# AVRI2CIO_V0_2_LEVEL0.net
KiCad netlist of a schematic drawn in EAGLE
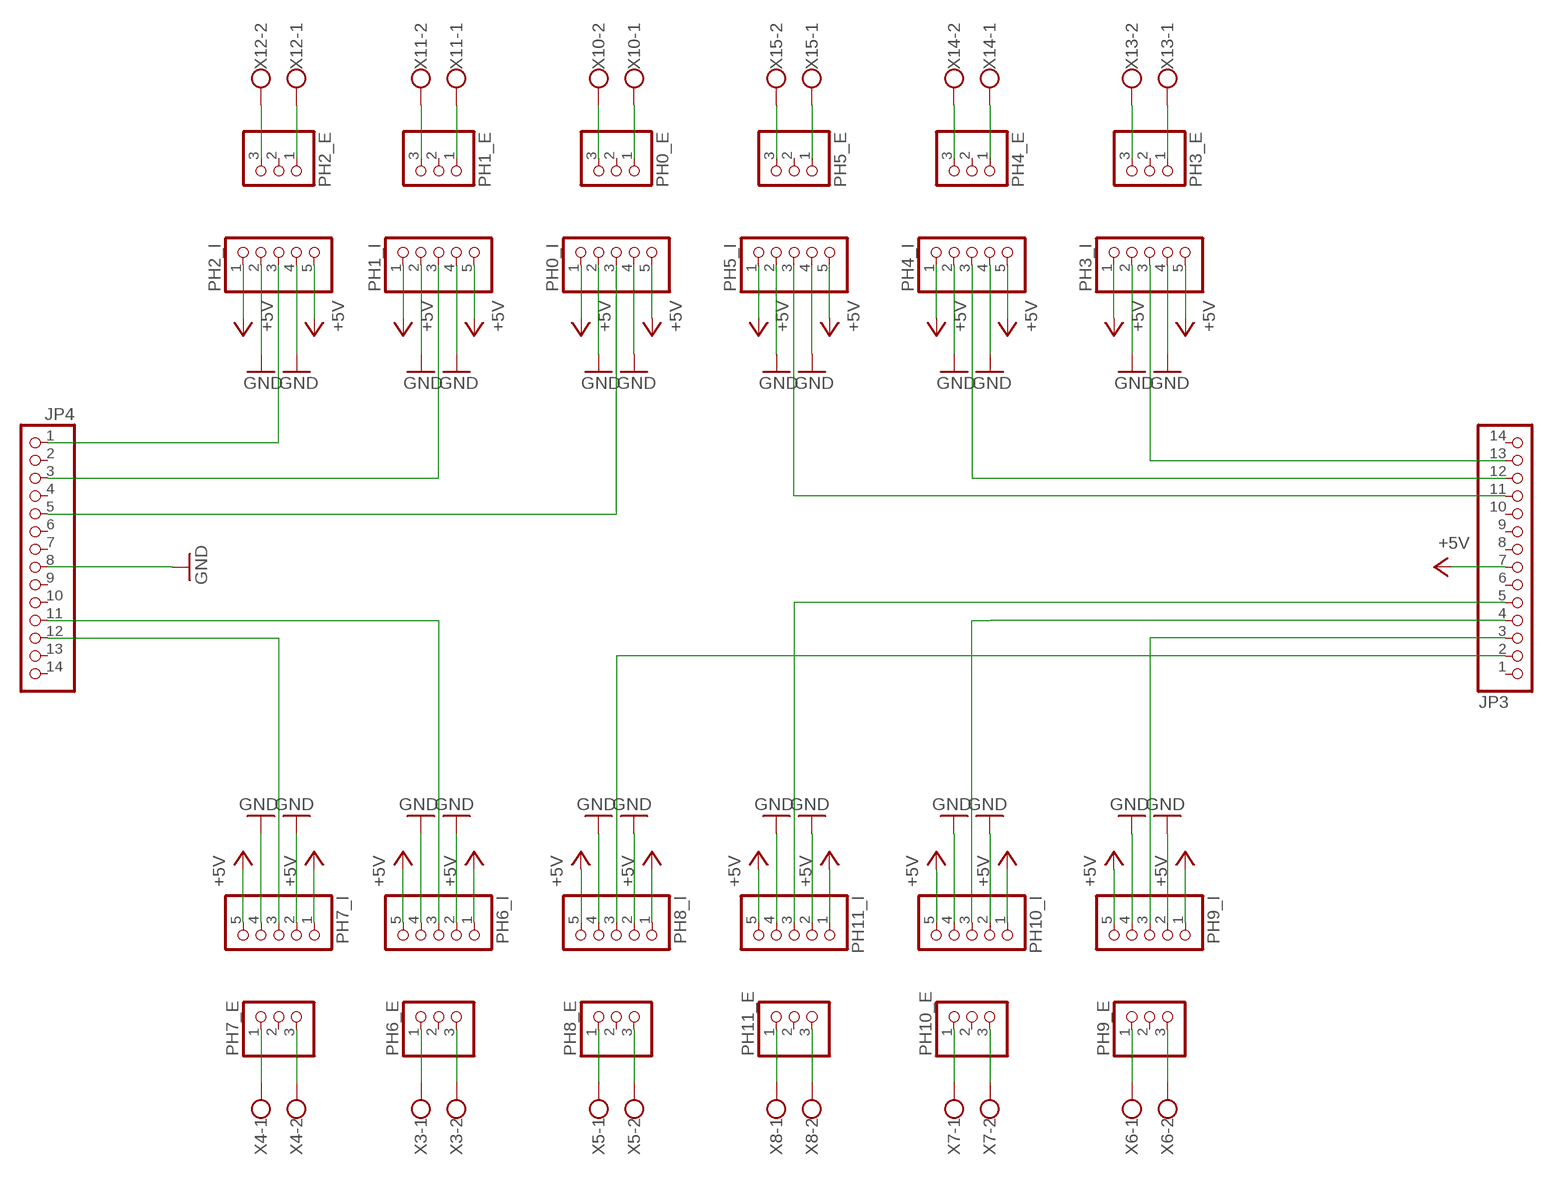
[diagram p0: schematic, sheet 1]

(export (version "E")
  (design (tool "Eeschema 10.0.6"))
  (components
    (comp (ref "JP3")
      (value "PINHD-1X14")
      (footprint "eagle-import:1X14")
      (libsource (lib "eagle-import") (part "PINHD-1X14"))
    )
    (comp (ref "JP4")
      (value "PINHD-1X14")
      (footprint "eagle-import:1X14")
      (libsource (lib "eagle-import") (part "PINHD-1X14"))
    )
    (comp (ref "PH0_E")
      (value "PINHD-1X3")
      (footprint "eagle-import:1X03")
      (libsource (lib "eagle-import") (part "PINHD-1X3"))
    )
    (comp (ref "PH0_I")
      (value "PINHD-1X5")
      (footprint "eagle-import:1X05")
      (libsource (lib "eagle-import") (part "PINHD-1X5"))
    )
    (comp (ref "PH1_E")
      (value "PINHD-1X3")
      (footprint "eagle-import:1X03")
      (libsource (lib "eagle-import") (part "PINHD-1X3"))
    )
    (comp (ref "PH1_I")
      (value "PINHD-1X5")
      (footprint "eagle-import:1X05")
      (libsource (lib "eagle-import") (part "PINHD-1X5"))
    )
    (comp (ref "PH2_E")
      (value "PINHD-1X3")
      (footprint "eagle-import:1X03")
      (libsource (lib "eagle-import") (part "PINHD-1X3"))
    )
    (comp (ref "PH2_I")
      (value "PINHD-1X5")
      (footprint "eagle-import:1X05")
      (libsource (lib "eagle-import") (part "PINHD-1X5"))
    )
    (comp (ref "PH3_E")
      (value "PINHD-1X3")
      (footprint "eagle-import:1X03")
      (libsource (lib "eagle-import") (part "PINHD-1X3"))
    )
    (comp (ref "PH3_I")
      (value "PINHD-1X5")
      (footprint "eagle-import:1X05")
      (libsource (lib "eagle-import") (part "PINHD-1X5"))
    )
    (comp (ref "PH4_E")
      (value "PINHD-1X3")
      (footprint "eagle-import:1X03")
      (libsource (lib "eagle-import") (part "PINHD-1X3"))
    )
    (comp (ref "PH4_I")
      (value "PINHD-1X5")
      (footprint "eagle-import:1X05")
      (libsource (lib "eagle-import") (part "PINHD-1X5"))
    )
    (comp (ref "PH5_E")
      (value "PINHD-1X3")
      (footprint "eagle-import:1X03")
      (libsource (lib "eagle-import") (part "PINHD-1X3"))
    )
    (comp (ref "PH5_I")
      (value "PINHD-1X5")
      (footprint "eagle-import:1X05")
      (libsource (lib "eagle-import") (part "PINHD-1X5"))
    )
    (comp (ref "PH6_E")
      (value "PINHD-1X3")
      (footprint "eagle-import:1X03")
      (libsource (lib "eagle-import") (part "PINHD-1X3"))
    )
    (comp (ref "PH6_I")
      (value "PINHD-1X5")
      (footprint "eagle-import:1X05")
      (libsource (lib "eagle-import") (part "PINHD-1X5"))
    )
    (comp (ref "PH7_E")
      (value "PINHD-1X3")
      (footprint "eagle-import:1X03")
      (libsource (lib "eagle-import") (part "PINHD-1X3"))
    )
    (comp (ref "PH7_I")
      (value "PINHD-1X5")
      (footprint "eagle-import:1X05")
      (libsource (lib "eagle-import") (part "PINHD-1X5"))
    )
    (comp (ref "PH8_E")
      (value "PINHD-1X3")
      (footprint "eagle-import:1X03")
      (libsource (lib "eagle-import") (part "PINHD-1X3"))
    )
    (comp (ref "PH8_I")
      (value "PINHD-1X5")
      (footprint "eagle-import:1X05")
      (libsource (lib "eagle-import") (part "PINHD-1X5"))
    )
    (comp (ref "PH9_E")
      (value "PINHD-1X3")
      (footprint "eagle-import:1X03")
      (libsource (lib "eagle-import") (part "PINHD-1X3"))
    )
    (comp (ref "PH9_I")
      (value "PINHD-1X5")
      (footprint "eagle-import:1X05")
      (libsource (lib "eagle-import") (part "PINHD-1X5"))
    )
    (comp (ref "PH10_E")
      (value "PINHD-1X3")
      (footprint "eagle-import:1X03")
      (libsource (lib "eagle-import") (part "PINHD-1X3"))
    )
    (comp (ref "PH10_I")
      (value "PINHD-1X5")
      (footprint "eagle-import:1X05")
      (libsource (lib "eagle-import") (part "PINHD-1X5"))
    )
    (comp (ref "PH11_E")
      (value "PINHD-1X3")
      (footprint "eagle-import:1X03")
      (libsource (lib "eagle-import") (part "PINHD-1X3"))
    )
    (comp (ref "PH11_I")
      (value "PINHD-1X5")
      (footprint "eagle-import:1X05")
      (libsource (lib "eagle-import") (part "PINHD-1X5"))
    )
    (comp (ref "X3")
      (value "W237-102")
      (footprint "eagle-import:W237-102")
      (fields (field (name "MPN") "237-102"))
      (libsource (lib "eagle-import") (part "W237-102"))
    )
    (comp (ref "X4")
      (value "W237-102")
      (footprint "eagle-import:W237-102")
      (fields (field (name "MPN") "237-102"))
      (libsource (lib "eagle-import") (part "W237-102"))
    )
    (comp (ref "X5")
      (value "W237-102")
      (footprint "eagle-import:W237-102")
      (fields (field (name "MPN") "237-102"))
      (libsource (lib "eagle-import") (part "W237-102"))
    )
    (comp (ref "X6")
      (value "W237-102")
      (footprint "eagle-import:W237-102")
      (fields (field (name "MPN") "237-102"))
      (libsource (lib "eagle-import") (part "W237-102"))
    )
    (comp (ref "X7")
      (value "W237-102")
      (footprint "eagle-import:W237-102")
      (fields (field (name "MPN") "237-102"))
      (libsource (lib "eagle-import") (part "W237-102"))
    )
    (comp (ref "X8")
      (value "W237-102")
      (footprint "eagle-import:W237-102")
      (fields (field (name "MPN") "237-102"))
      (libsource (lib "eagle-import") (part "W237-102"))
    )
    (comp (ref "X10")
      (value "W237-102")
      (footprint "eagle-import:W237-102")
      (fields
        (field (name "MPN") "237-102")
        (field (name "MPN_1") "237-102")
        (field (name "OC_FARNELL") "unknown")
        (field (name "OC_NEWARK") "70K9898")
      )
      (libsource (lib "eagle-import") (part "W237-102"))
    )
    (comp (ref "X11")
      (value "W237-102")
      (footprint "eagle-import:W237-102")
      (fields (field (name "MPN") "237-102"))
      (libsource (lib "eagle-import") (part "W237-102"))
    )
    (comp (ref "X12")
      (value "W237-102")
      (footprint "eagle-import:W237-102")
      (fields (field (name "MPN") "237-102"))
      (libsource (lib "eagle-import") (part "W237-102"))
    )
    (comp (ref "X13")
      (value "W237-102")
      (footprint "eagle-import:W237-102")
      (fields (field (name "MPN") "237-102"))
      (libsource (lib "eagle-import") (part "W237-102"))
    )
    (comp (ref "X14")
      (value "W237-102")
      (footprint "eagle-import:W237-102")
      (fields (field (name "MPN") "237-102"))
      (libsource (lib "eagle-import") (part "W237-102"))
    )
    (comp (ref "X15")
      (value "W237-102")
      (footprint "eagle-import:W237-102")
      (fields (field (name "MPN") "237-102"))
      (libsource (lib "eagle-import") (part "W237-102"))
    )
  )
  (nets
    (net (code "1") (name "+5V") (class "Default")
      (node (ref "JP3") (pin "7") (pinfunction "7_7") (pintype "passive"))
      (node (ref "PH0_I") (pin "1") (pinfunction "1_1") (pintype "passive"))
      (node (ref "PH0_I") (pin "5") (pinfunction "5_5") (pintype "passive"))
      (node (ref "PH10_I") (pin "1") (pinfunction "1_1") (pintype "passive"))
      (node (ref "PH10_I") (pin "5") (pinfunction "5_5") (pintype "passive"))
      (node (ref "PH11_I") (pin "1") (pinfunction "1_1") (pintype "passive"))
      (node (ref "PH11_I") (pin "5") (pinfunction "5_5") (pintype "passive"))
      (node (ref "PH1_I") (pin "1") (pinfunction "1_1") (pintype "passive"))
      (node (ref "PH1_I") (pin "5") (pinfunction "5_5") (pintype "passive"))
      (node (ref "PH2_I") (pin "1") (pinfunction "1_1") (pintype "passive"))
      (node (ref "PH2_I") (pin "5") (pinfunction "5_5") (pintype "passive"))
      (node (ref "PH3_I") (pin "1") (pinfunction "1_1") (pintype "passive"))
      (node (ref "PH3_I") (pin "5") (pinfunction "5_5") (pintype "passive"))
      (node (ref "PH4_I") (pin "1") (pinfunction "1_1") (pintype "passive"))
      (node (ref "PH4_I") (pin "5") (pinfunction "5_5") (pintype "passive"))
      (node (ref "PH5_I") (pin "1") (pinfunction "1_1") (pintype "passive"))
      (node (ref "PH5_I") (pin "5") (pinfunction "5_5") (pintype "passive"))
      (node (ref "PH6_I") (pin "1") (pinfunction "1_1") (pintype "passive"))
      (node (ref "PH6_I") (pin "5") (pinfunction "5_5") (pintype "passive"))
      (node (ref "PH7_I") (pin "1") (pinfunction "1_1") (pintype "passive"))
      (node (ref "PH7_I") (pin "5") (pinfunction "5_5") (pintype "passive"))
      (node (ref "PH8_I") (pin "1") (pinfunction "1_1") (pintype "passive"))
      (node (ref "PH8_I") (pin "5") (pinfunction "5_5") (pintype "passive"))
      (node (ref "PH9_I") (pin "1") (pinfunction "1_1") (pintype "passive"))
      (node (ref "PH9_I") (pin "5") (pinfunction "5_5") (pintype "passive"))
    )
    (net (code "2") (name "GND") (class "Default")
      (node (ref "JP4") (pin "8") (pinfunction "8_8") (pintype "passive"))
      (node (ref "PH0_I") (pin "2") (pinfunction "2_2") (pintype "passive"))
      (node (ref "PH0_I") (pin "4") (pinfunction "4_4") (pintype "passive"))
      (node (ref "PH10_I") (pin "2") (pinfunction "2_2") (pintype "passive"))
      (node (ref "PH10_I") (pin "4") (pinfunction "4_4") (pintype "passive"))
      (node (ref "PH11_I") (pin "2") (pinfunction "2_2") (pintype "passive"))
      (node (ref "PH11_I") (pin "4") (pinfunction "4_4") (pintype "passive"))
      (node (ref "PH1_I") (pin "2") (pinfunction "2_2") (pintype "passive"))
      (node (ref "PH1_I") (pin "4") (pinfunction "4_4") (pintype "passive"))
      (node (ref "PH2_I") (pin "2") (pinfunction "2_2") (pintype "passive"))
      (node (ref "PH2_I") (pin "4") (pinfunction "4_4") (pintype "passive"))
      (node (ref "PH3_I") (pin "2") (pinfunction "2_2") (pintype "passive"))
      (node (ref "PH3_I") (pin "4") (pinfunction "4_4") (pintype "passive"))
      (node (ref "PH4_I") (pin "2") (pinfunction "2_2") (pintype "passive"))
      (node (ref "PH4_I") (pin "4") (pinfunction "4_4") (pintype "passive"))
      (node (ref "PH5_I") (pin "2") (pinfunction "2_2") (pintype "passive"))
      (node (ref "PH5_I") (pin "4") (pinfunction "4_4") (pintype "passive"))
      (node (ref "PH6_I") (pin "2") (pinfunction "2_2") (pintype "passive"))
      (node (ref "PH6_I") (pin "4") (pinfunction "4_4") (pintype "passive"))
      (node (ref "PH7_I") (pin "2") (pinfunction "2_2") (pintype "passive"))
      (node (ref "PH7_I") (pin "4") (pinfunction "4_4") (pintype "passive"))
      (node (ref "PH8_I") (pin "2") (pinfunction "2_2") (pintype "passive"))
      (node (ref "PH8_I") (pin "4") (pinfunction "4_4") (pintype "passive"))
      (node (ref "PH9_I") (pin "2") (pinfunction "2_2") (pintype "passive"))
      (node (ref "PH9_I") (pin "4") (pinfunction "4_4") (pintype "passive"))
    )
    (net (code "3") (name "Net-(JP3-Pad2)") (class "Default")
      (node (ref "JP3") (pin "2") (pinfunction "2_2") (pintype "passive"))
      (node (ref "PH8_I") (pin "3") (pinfunction "3_3") (pintype "passive"))
    )
    (net (code "4") (name "Net-(JP3-Pad3)") (class "Default")
      (node (ref "JP3") (pin "3") (pinfunction "3_3") (pintype "passive"))
      (node (ref "PH9_I") (pin "3") (pinfunction "3_3") (pintype "passive"))
    )
    (net (code "5") (name "Net-(JP3-Pad4)") (class "Default")
      (node (ref "JP3") (pin "4") (pinfunction "4_4") (pintype "passive"))
      (node (ref "PH10_I") (pin "3") (pinfunction "3_3") (pintype "passive"))
    )
    (net (code "6") (name "Net-(JP3-Pad5)") (class "Default")
      (node (ref "JP3") (pin "5") (pinfunction "5_5") (pintype "passive"))
      (node (ref "PH11_I") (pin "3") (pinfunction "3_3") (pintype "passive"))
    )
    (net (code "7") (name "Net-(JP3-Pad11)") (class "Default")
      (node (ref "JP3") (pin "11") (pinfunction "11_11") (pintype "passive"))
      (node (ref "PH5_I") (pin "3") (pinfunction "3_3") (pintype "passive"))
    )
    (net (code "8") (name "Net-(JP3-Pad12)") (class "Default")
      (node (ref "JP3") (pin "12") (pinfunction "12_12") (pintype "passive"))
      (node (ref "PH4_I") (pin "3") (pinfunction "3_3") (pintype "passive"))
    )
    (net (code "9") (name "Net-(JP3-Pad13)") (class "Default")
      (node (ref "JP3") (pin "13") (pinfunction "13_13") (pintype "passive"))
      (node (ref "PH3_I") (pin "3") (pinfunction "3_3") (pintype "passive"))
    )
    (net (code "10") (name "Net-(JP4-Pad1)") (class "Default")
      (node (ref "JP4") (pin "1") (pinfunction "1_1") (pintype "passive"))
      (node (ref "PH2_I") (pin "3") (pinfunction "3_3") (pintype "passive"))
    )
    (net (code "11") (name "Net-(JP4-Pad3)") (class "Default")
      (node (ref "JP4") (pin "3") (pinfunction "3_3") (pintype "passive"))
      (node (ref "PH1_I") (pin "3") (pinfunction "3_3") (pintype "passive"))
    )
    (net (code "12") (name "Net-(JP4-Pad5)") (class "Default")
      (node (ref "JP4") (pin "5") (pinfunction "5_5") (pintype "passive"))
      (node (ref "PH0_I") (pin "3") (pinfunction "3_3") (pintype "passive"))
    )
    (net (code "13") (name "Net-(JP4-Pad11)") (class "Default")
      (node (ref "JP4") (pin "11") (pinfunction "11_11") (pintype "passive"))
      (node (ref "PH6_I") (pin "3") (pinfunction "3_3") (pintype "passive"))
    )
    (net (code "14") (name "Net-(JP4-Pad12)") (class "Default")
      (node (ref "JP4") (pin "12") (pinfunction "12_12") (pintype "passive"))
      (node (ref "PH7_I") (pin "3") (pinfunction "3_3") (pintype "passive"))
    )
    (net (code "15") (name "Net-(X3A-KL)") (class "Default")
      (node (ref "PH6_E") (pin "1") (pinfunction "1_1") (pintype "passive"))
      (node (ref "X3") (pin "1") (pinfunction "KL_1") (pintype "passive"))
    )
    (net (code "16") (name "Net-(X3B-KL)") (class "Default")
      (node (ref "PH6_E") (pin "3") (pinfunction "3_3") (pintype "passive"))
      (node (ref "X3") (pin "2") (pinfunction "KL_2") (pintype "passive"))
    )
    (net (code "17") (name "Net-(X4A-KL)") (class "Default")
      (node (ref "PH7_E") (pin "1") (pinfunction "1_1") (pintype "passive"))
      (node (ref "X4") (pin "1") (pinfunction "KL_1") (pintype "passive"))
    )
    (net (code "18") (name "Net-(X4B-KL)") (class "Default")
      (node (ref "PH7_E") (pin "3") (pinfunction "3_3") (pintype "passive"))
      (node (ref "X4") (pin "2") (pinfunction "KL_2") (pintype "passive"))
    )
    (net (code "19") (name "Net-(X5A-KL)") (class "Default")
      (node (ref "PH8_E") (pin "1") (pinfunction "1_1") (pintype "passive"))
      (node (ref "X5") (pin "1") (pinfunction "KL_1") (pintype "passive"))
    )
    (net (code "20") (name "Net-(X5B-KL)") (class "Default")
      (node (ref "PH8_E") (pin "3") (pinfunction "3_3") (pintype "passive"))
      (node (ref "X5") (pin "2") (pinfunction "KL_2") (pintype "passive"))
    )
    (net (code "21") (name "Net-(X6A-KL)") (class "Default")
      (node (ref "PH9_E") (pin "1") (pinfunction "1_1") (pintype "passive"))
      (node (ref "X6") (pin "1") (pinfunction "KL_1") (pintype "passive"))
    )
    (net (code "22") (name "Net-(X6B-KL)") (class "Default")
      (node (ref "PH9_E") (pin "3") (pinfunction "3_3") (pintype "passive"))
      (node (ref "X6") (pin "2") (pinfunction "KL_2") (pintype "passive"))
    )
    (net (code "23") (name "Net-(X7A-KL)") (class "Default")
      (node (ref "PH10_E") (pin "1") (pinfunction "1_1") (pintype "passive"))
      (node (ref "X7") (pin "1") (pinfunction "KL_1") (pintype "passive"))
    )
    (net (code "24") (name "Net-(X7B-KL)") (class "Default")
      (node (ref "PH10_E") (pin "3") (pinfunction "3_3") (pintype "passive"))
      (node (ref "X7") (pin "2") (pinfunction "KL_2") (pintype "passive"))
    )
    (net (code "25") (name "Net-(X8A-KL)") (class "Default")
      (node (ref "PH11_E") (pin "1") (pinfunction "1_1") (pintype "passive"))
      (node (ref "X8") (pin "1") (pinfunction "KL_1") (pintype "passive"))
    )
    (net (code "26") (name "Net-(X8B-KL)") (class "Default")
      (node (ref "PH11_E") (pin "3") (pinfunction "3_3") (pintype "passive"))
      (node (ref "X8") (pin "2") (pinfunction "KL_2") (pintype "passive"))
    )
    (net (code "27") (name "Net-(X10A-KL)") (class "Default")
      (node (ref "PH0_E") (pin "1") (pinfunction "1_1") (pintype "passive"))
      (node (ref "X10") (pin "1") (pinfunction "KL_1") (pintype "passive"))
    )
    (net (code "28") (name "Net-(X10B-KL)") (class "Default")
      (node (ref "PH0_E") (pin "3") (pinfunction "3_3") (pintype "passive"))
      (node (ref "X10") (pin "2") (pinfunction "KL_2") (pintype "passive"))
    )
    (net (code "29") (name "Net-(X11A-KL)") (class "Default")
      (node (ref "PH1_E") (pin "1") (pinfunction "1_1") (pintype "passive"))
      (node (ref "X11") (pin "1") (pinfunction "KL_1") (pintype "passive"))
    )
    (net (code "30") (name "Net-(X11B-KL)") (class "Default")
      (node (ref "PH1_E") (pin "3") (pinfunction "3_3") (pintype "passive"))
      (node (ref "X11") (pin "2") (pinfunction "KL_2") (pintype "passive"))
    )
    (net (code "31") (name "Net-(X12A-KL)") (class "Default")
      (node (ref "PH2_E") (pin "1") (pinfunction "1_1") (pintype "passive"))
      (node (ref "X12") (pin "1") (pinfunction "KL_1") (pintype "passive"))
    )
    (net (code "32") (name "Net-(X12B-KL)") (class "Default")
      (node (ref "PH2_E") (pin "3") (pinfunction "3_3") (pintype "passive"))
      (node (ref "X12") (pin "2") (pinfunction "KL_2") (pintype "passive"))
    )
    (net (code "33") (name "Net-(X13A-KL)") (class "Default")
      (node (ref "PH3_E") (pin "1") (pinfunction "1_1") (pintype "passive"))
      (node (ref "X13") (pin "1") (pinfunction "KL_1") (pintype "passive"))
    )
    (net (code "34") (name "Net-(X13B-KL)") (class "Default")
      (node (ref "PH3_E") (pin "3") (pinfunction "3_3") (pintype "passive"))
      (node (ref "X13") (pin "2") (pinfunction "KL_2") (pintype "passive"))
    )
    (net (code "35") (name "Net-(X14A-KL)") (class "Default")
      (node (ref "PH4_E") (pin "1") (pinfunction "1_1") (pintype "passive"))
      (node (ref "X14") (pin "1") (pinfunction "KL_1") (pintype "passive"))
    )
    (net (code "36") (name "Net-(X14B-KL)") (class "Default")
      (node (ref "PH4_E") (pin "3") (pinfunction "3_3") (pintype "passive"))
      (node (ref "X14") (pin "2") (pinfunction "KL_2") (pintype "passive"))
    )
    (net (code "37") (name "Net-(X15A-KL)") (class "Default")
      (node (ref "PH5_E") (pin "1") (pinfunction "1_1") (pintype "passive"))
      (node (ref "X15") (pin "1") (pinfunction "KL_1") (pintype "passive"))
    )
    (net (code "38") (name "Net-(X15B-KL)") (class "Default")
      (node (ref "PH5_E") (pin "3") (pinfunction "3_3") (pintype "passive"))
      (node (ref "X15") (pin "2") (pinfunction "KL_2") (pintype "passive"))
    )
    (net (code "39") (name "unconnected-(JP3-Pad1)") (class "Default")
      (node (ref "JP3") (pin "1") (pinfunction "1_1") (pintype "passive"))
    )
    (net (code "40") (name "unconnected-(JP3-Pad6)") (class "Default")
      (node (ref "JP3") (pin "6") (pinfunction "6_6") (pintype "passive"))
    )
    (net (code "41") (name "unconnected-(JP3-Pad8)") (class "Default")
      (node (ref "JP3") (pin "8") (pinfunction "8_8") (pintype "passive"))
    )
    (net (code "42") (name "unconnected-(JP3-Pad9)") (class "Default")
      (node (ref "JP3") (pin "9") (pinfunction "9_9") (pintype "passive"))
    )
    (net (code "43") (name "unconnected-(JP3-Pad10)") (class "Default")
      (node (ref "JP3") (pin "10") (pinfunction "10_10") (pintype "passive"))
    )
    (net (code "44") (name "unconnected-(JP3-Pad14)") (class "Default")
      (node (ref "JP3") (pin "14") (pinfunction "14_14") (pintype "passive"))
    )
    (net (code "45") (name "unconnected-(JP4-Pad2)") (class "Default")
      (node (ref "JP4") (pin "2") (pinfunction "2_2") (pintype "passive"))
    )
    (net (code "46") (name "unconnected-(JP4-Pad4)") (class "Default")
      (node (ref "JP4") (pin "4") (pinfunction "4_4") (pintype "passive"))
    )
    (net (code "47") (name "unconnected-(JP4-Pad6)") (class "Default")
      (node (ref "JP4") (pin "6") (pinfunction "6_6") (pintype "passive"))
    )
    (net (code "48") (name "unconnected-(JP4-Pad7)") (class "Default")
      (node (ref "JP4") (pin "7") (pinfunction "7_7") (pintype "passive"))
    )
    (net (code "49") (name "unconnected-(JP4-Pad9)") (class "Default")
      (node (ref "JP4") (pin "9") (pinfunction "9_9") (pintype "passive"))
    )
    (net (code "50") (name "unconnected-(JP4-Pad10)") (class "Default")
      (node (ref "JP4") (pin "10") (pinfunction "10_10") (pintype "passive"))
    )
    (net (code "51") (name "unconnected-(JP4-Pad13)") (class "Default")
      (node (ref "JP4") (pin "13") (pinfunction "13_13") (pintype "passive"))
    )
    (net (code "52") (name "unconnected-(JP4-Pad14)") (class "Default")
      (node (ref "JP4") (pin "14") (pinfunction "14_14") (pintype "passive"))
    )
    (net (code "53") (name "unconnected-(PH0_E-Pad2)") (class "Default")
      (node (ref "PH0_E") (pin "2") (pinfunction "2_2") (pintype "passive"))
    )
    (net (code "54") (name "unconnected-(PH1_E-Pad2)") (class "Default")
      (node (ref "PH1_E") (pin "2") (pinfunction "2_2") (pintype "passive"))
    )
    (net (code "55") (name "unconnected-(PH2_E-Pad2)") (class "Default")
      (node (ref "PH2_E") (pin "2") (pinfunction "2_2") (pintype "passive"))
    )
    (net (code "56") (name "unconnected-(PH3_E-Pad2)") (class "Default")
      (node (ref "PH3_E") (pin "2") (pinfunction "2_2") (pintype "passive"))
    )
    (net (code "57") (name "unconnected-(PH4_E-Pad2)") (class "Default")
      (node (ref "PH4_E") (pin "2") (pinfunction "2_2") (pintype "passive"))
    )
    (net (code "58") (name "unconnected-(PH5_E-Pad2)") (class "Default")
      (node (ref "PH5_E") (pin "2") (pinfunction "2_2") (pintype "passive"))
    )
    (net (code "59") (name "unconnected-(PH6_E-Pad2)") (class "Default")
      (node (ref "PH6_E") (pin "2") (pinfunction "2_2") (pintype "passive"))
    )
    (net (code "60") (name "unconnected-(PH7_E-Pad2)") (class "Default")
      (node (ref "PH7_E") (pin "2") (pinfunction "2_2") (pintype "passive"))
    )
    (net (code "61") (name "unconnected-(PH8_E-Pad2)") (class "Default")
      (node (ref "PH8_E") (pin "2") (pinfunction "2_2") (pintype "passive"))
    )
    (net (code "62") (name "unconnected-(PH9_E-Pad2)") (class "Default")
      (node (ref "PH9_E") (pin "2") (pinfunction "2_2") (pintype "passive"))
    )
    (net (code "63") (name "unconnected-(PH10_E-Pad2)") (class "Default")
      (node (ref "PH10_E") (pin "2") (pinfunction "2_2") (pintype "passive"))
    )
    (net (code "64") (name "unconnected-(PH11_E-Pad2)") (class "Default")
      (node (ref "PH11_E") (pin "2") (pinfunction "2_2") (pintype "passive"))
    )
  )
)
